# LittleButtons.net
KiCad netlist of a schematic drawn in Altium Designer
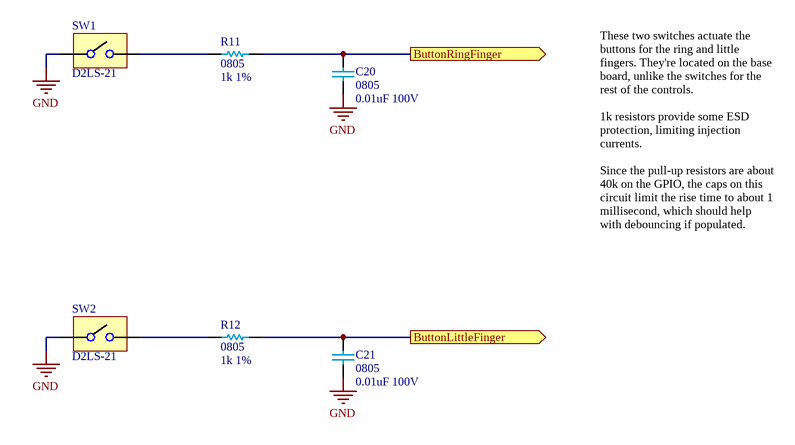
[diagram p0: LittleButtons.SchDoc]

(export (version "E")
  (design (tool "Eeschema 10.0.6"))
  (components
    (comp (ref "C20")
      (value "0805")
      (footprint "C0603")
      (description "0805, X5R or better")
      (fields (field (name "ALTIUM_VALUE") "0.01uF 100V"))
      (libsource (lib "Chip_Passives") (part "Cap 0.01uF 100V"))
    )
    (comp (ref "C21")
      (value "0805")
      (footprint "C0603")
      (description "0805, X5R or better")
      (fields (field (name "ALTIUM_VALUE") "0.01uF 100V"))
      (libsource (lib "Chip_Passives") (part "Cap 0.01uF 100V"))
    )
    (comp (ref "R11")
      (value "0805")
      (footprint "0603")
      (description "Chip resistor, 1/8W 100PPM")
      (fields (field (name "ALTIUM_VALUE") "1k 1%"))
      (libsource (lib "Chip_Passives") (part "Res 1k 1% 0805"))
    )
    (comp (ref "R12")
      (value "0805")
      (footprint "0603")
      (description "Chip resistor, 1/8W 100PPM")
      (fields (field (name "ALTIUM_VALUE") "1k 1%"))
      (libsource (lib "Chip_Passives") (part "Res 1k 1% 0805"))
    )
    (comp (ref "SW1")
      (value "D2LS-21")
      (footprint "D2LS-21")
      (description "Compact Surface-mounting Switch for long durability")
      (libsource (lib "Switches") (part "D2LS-21"))
    )
    (comp (ref "SW2")
      (value "D2LS-21")
      (footprint "D2LS-21")
      (description "Compact Surface-mounting Switch for long durability")
      (libsource (lib "Switches") (part "D2LS-21"))
    )
  )
  (nets
    (net (code "1") (name "/ButtonLittleFinger") (class "Default")
      (node (ref "C21") (pin "2") (pinfunction "2_2") (pintype "passive"))
      (node (ref "R12") (pin "2") (pinfunction "2_2") (pintype "passive"))
    )
    (net (code "2") (name "/ButtonRingFinger") (class "Default")
      (node (ref "C20") (pin "2") (pinfunction "2_2") (pintype "passive"))
      (node (ref "R11") (pin "2") (pinfunction "2_2") (pintype "passive"))
    )
    (net (code "3") (name "GND") (class "Default")
      (node (ref "C20") (pin "1") (pinfunction "1_1") (pintype "passive"))
      (node (ref "C21") (pin "1") (pinfunction "1_1") (pintype "passive"))
      (node (ref "SW1") (pin "A") (pinfunction "A_A") (pintype "passive"))
      (node (ref "SW2") (pin "A") (pinfunction "A_A") (pintype "passive"))
    )
    (net (code "4") (name "Net-(R11-Pad1)") (class "Default")
      (node (ref "R11") (pin "1") (pinfunction "1_1") (pintype "passive"))
      (node (ref "SW1") (pin "B") (pinfunction "B_B") (pintype "passive"))
    )
    (net (code "5") (name "Net-(R12-Pad1)") (class "Default")
      (node (ref "R12") (pin "1") (pinfunction "1_1") (pintype "passive"))
      (node (ref "SW2") (pin "B") (pinfunction "B_B") (pintype "passive"))
    )
  )
)
